# Schematic.net
KiCad netlist of a schematic drawn in Altium Designer
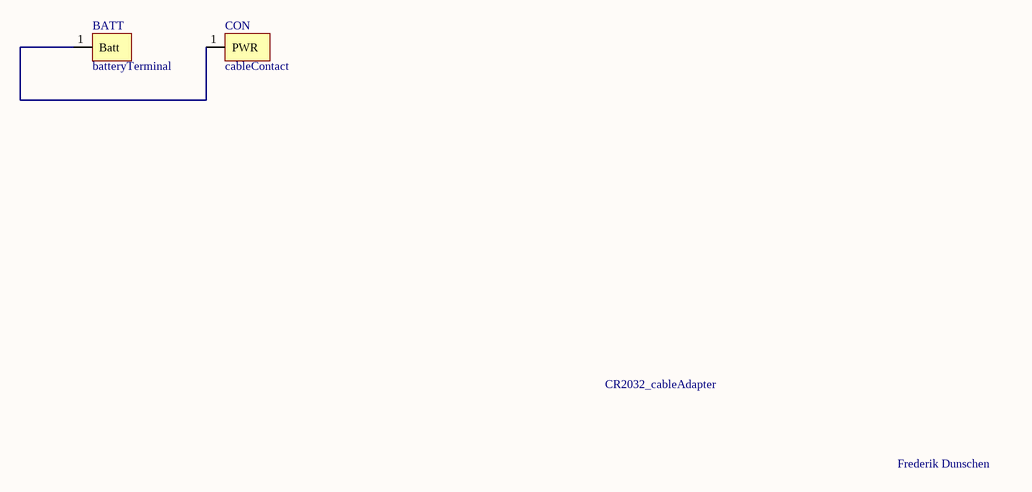
[diagram p0: Schematic.SchDoc]

(export (version "E")
  (design (tool "Eeschema 10.0.6"))
  (components
    (comp (ref "BATT")
      (value "batteryTerminal")
      (footprint "PCBComponent_1")
      (libsource (lib "Schlib") (part "batteryTerminal"))
    )
    (comp (ref "CON")
      (value "cableContact")
      (footprint "CABLECONTQACT")
      (libsource (lib "Schlib") (part "cableContact"))
    )
  )
  (nets
    (net (code "1") (name "Net-(BATT-Batt)") (class "Default")
      (node (ref "BATT") (pin "1") (pinfunction "Batt_1") (pintype "power_in"))
      (node (ref "CON") (pin "1") (pinfunction "PWR_1") (pintype "power_in"))
    )
  )
)
